# DAC_channel.net
KiCad netlist of a schematic drawn in Altium Designer
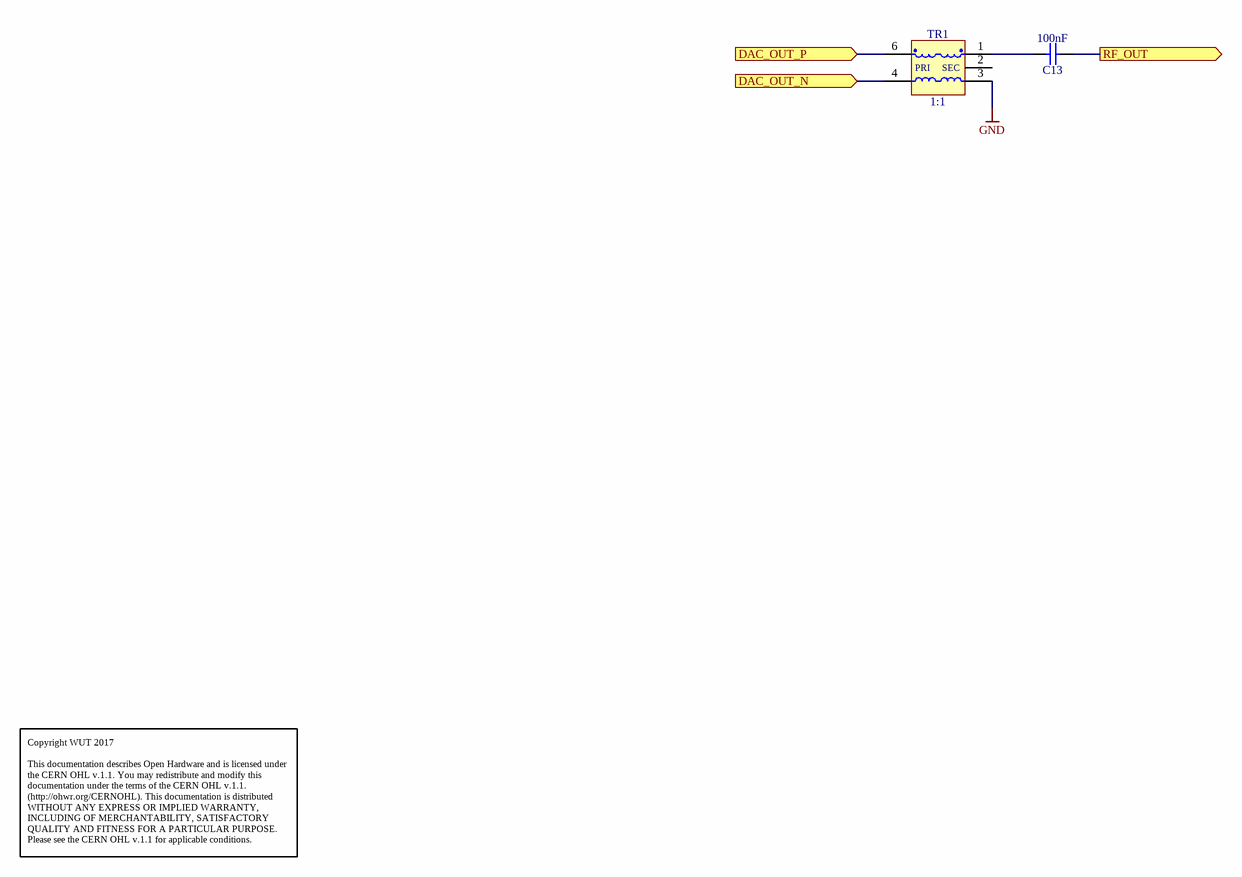
[diagram p0: DAC_channel.SchDoc]

(export (version "E")
  (design (tool "Eeschema 10.0.6"))
  (components
    (comp (ref "C13")
      (value "100nF")
      (footprint "CAPC1608X87N")
      (description "Non-polarised capacitor")
      (fields
        (field (name "PART NUMBER") "CC0603_100NF_50V_10%_X7R")
        (field (name "VOLTAGE") "50V")
        (field (name "AUTHOR") "CERN DEM JLC")
      )
      (libsource (lib "Capacitors") (part "Capacitor - non polarized"))
    )
    (comp (ref "TR1")
      (value "1:1")
      (footprint "XFMR_MINI-CIRCUITS_AT224")
      (description "50 Ohms 4.5 To 3000MHz RF Transformers")
      (fields
        (field (name "PART NUMBER") "XFMR_MINI-CIRCUITS_TC1-1-13M+")
        (field (name "MANUFACTURER") "MINI-CIRCUITS")
        (field (name "AUTHOR") "CERN DEM JLC")
      )
      (libsource (lib "Inductors & Transformers") (part "XFMR_MINI-CIRCUITS_TC1-1-13M+"))
    )
  )
  (nets
    (net (code "1") (name "/DAC_OUT_N") (class "Default")
      (node (ref "TR1") (pin "4") (pinfunction "P_4") (pintype "passive"))
    )
    (net (code "2") (name "/DAC_OUT_P") (class "Default")
      (node (ref "TR1") (pin "6") (pinfunction "PDOT_6") (pintype "passive"))
    )
    (net (code "3") (name "/RF_OUT") (class "Default")
      (node (ref "C13") (pin "1") (pinfunction "1_1") (pintype "passive"))
    )
    (net (code "4") (name "GND") (class "Default")
      (node (ref "TR1") (pin "3") (pinfunction "S_3") (pintype "passive"))
    )
    (net (code "5") (name "Net-(TR1-SDOT)") (class "Default")
      (node (ref "C13") (pin "2") (pinfunction "2_2") (pintype "passive"))
      (node (ref "TR1") (pin "1") (pinfunction "SDOT_1") (pintype "passive"))
    )
    (net (code "6") (name "unconnected-(TR1-NC-Pad2)") (class "Default")
      (node (ref "TR1") (pin "2") (pinfunction "NC_2") (pintype "passive"))
    )
  )
)
